# 1_54in.net
KiCad netlist of a schematic drawn in EAGLE
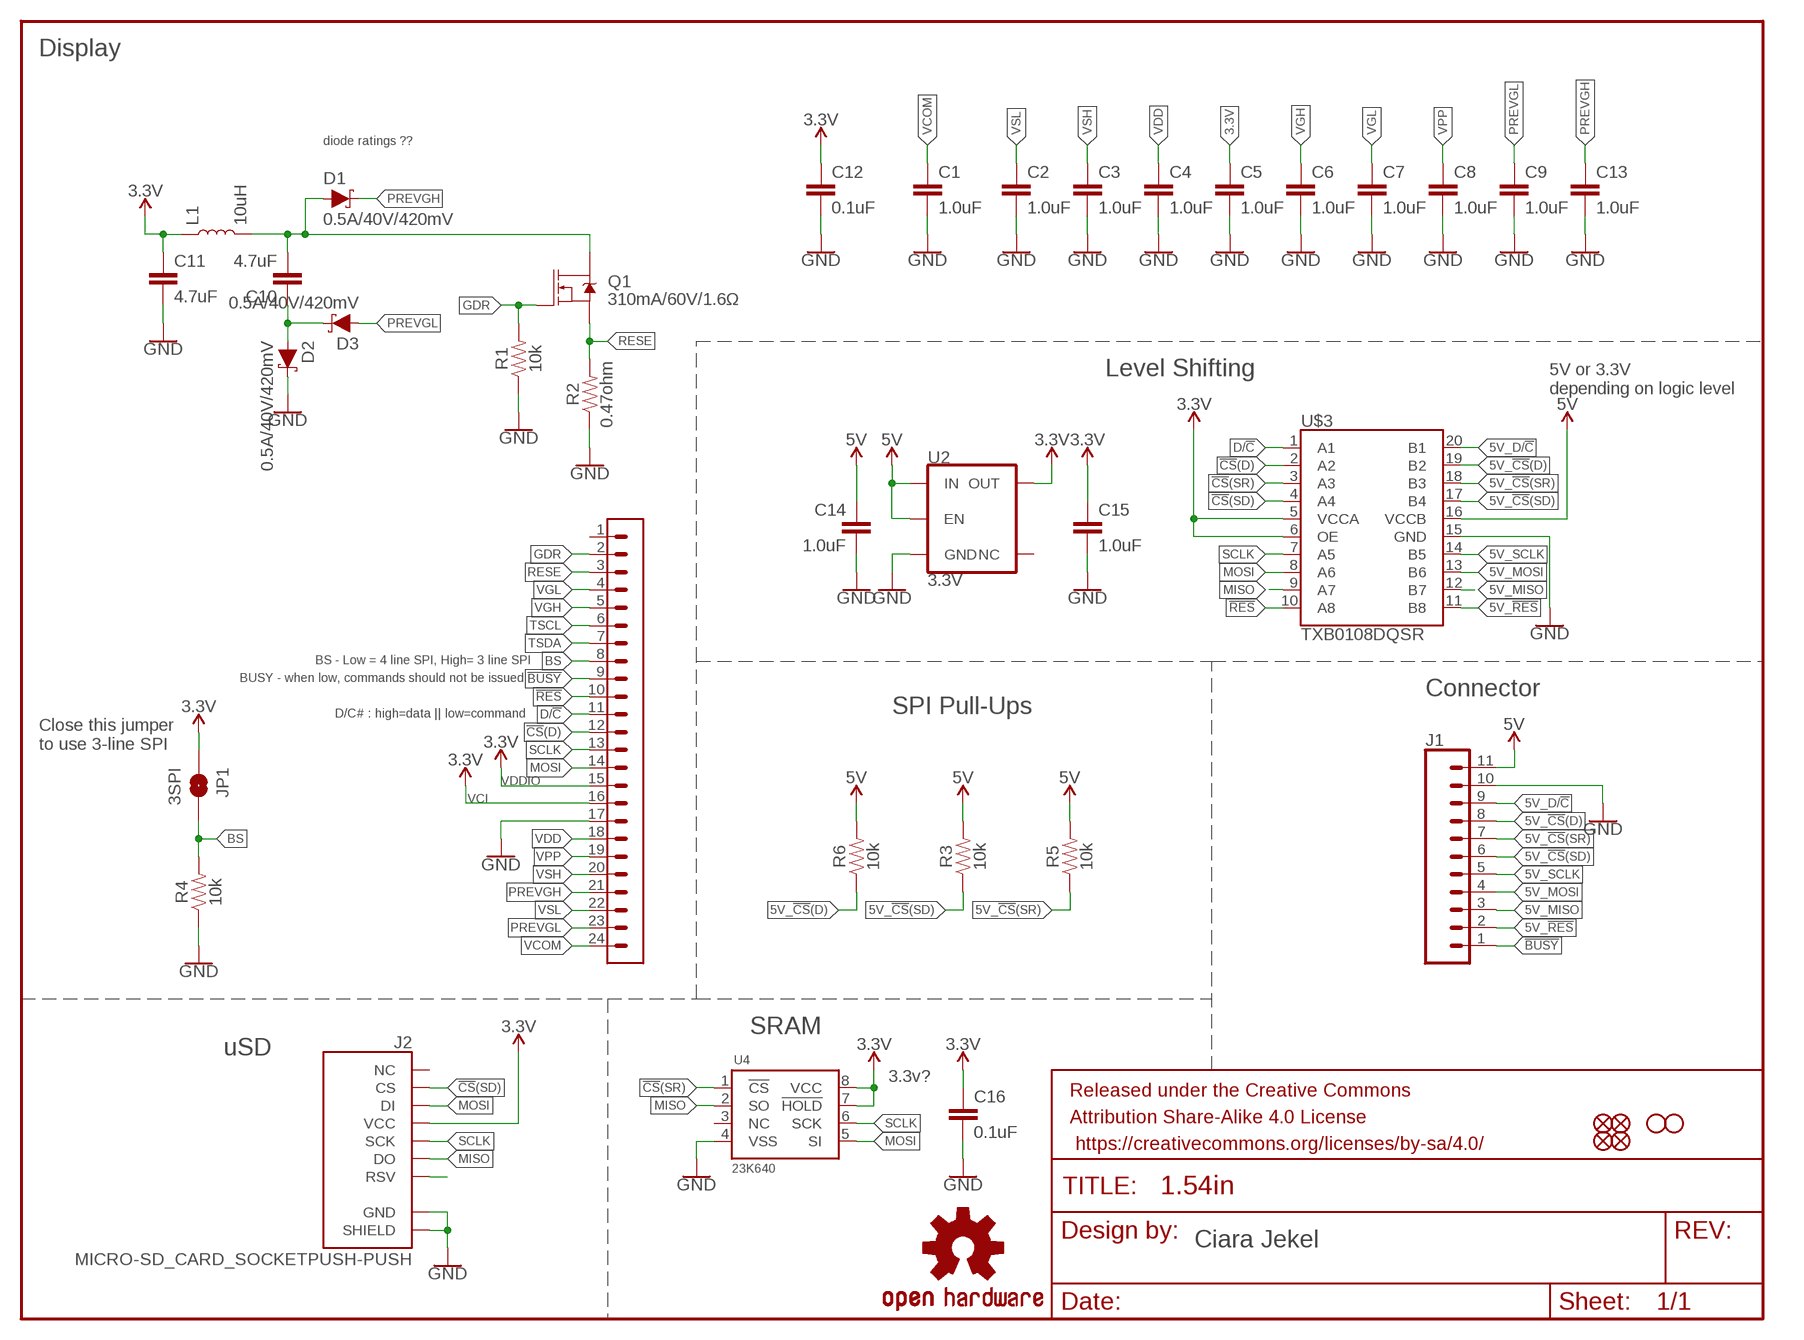
[diagram p0: schematic, sheet 1]

(export (version "E")
  (design (tool "Eeschema 10.0.6"))
  (components
    (comp (ref "C1")
      (value "1.0uF")
      (footprint "eagle-import:0603")
      (libsource (lib "eagle-import") (part "1.0UF-0603-16V-10%"))
    )
    (comp (ref "C2")
      (value "1.0uF")
      (footprint "eagle-import:0805")
      (libsource (lib "eagle-import") (part "1.0UF-0805-25V-10%"))
    )
    (comp (ref "C3")
      (value "1.0uF")
      (footprint "eagle-import:0805")
      (libsource (lib "eagle-import") (part "1.0UF-0805-25V-10%"))
    )
    (comp (ref "C4")
      (value "1.0uF")
      (footprint "eagle-import:0805")
      (libsource (lib "eagle-import") (part "1.0UF-0805-25V-10%"))
    )
    (comp (ref "C5")
      (value "1.0uF")
      (footprint "eagle-import:0805")
      (libsource (lib "eagle-import") (part "1.0UF-0805-25V-10%"))
    )
    (comp (ref "C6")
      (value "1.0uF")
      (footprint "eagle-import:0805")
      (libsource (lib "eagle-import") (part "1.0UF-0805-25V-10%"))
    )
    (comp (ref "C7")
      (value "1.0uF")
      (footprint "eagle-import:0805")
      (libsource (lib "eagle-import") (part "1.0UF-0805-25V-10%"))
    )
    (comp (ref "C8")
      (value "1.0uF")
      (footprint "eagle-import:0805")
      (libsource (lib "eagle-import") (part "1.0UF-0805-25V-10%"))
    )
    (comp (ref "C9")
      (value "1.0uF")
      (footprint "eagle-import:0805")
      (libsource (lib "eagle-import") (part "1.0UF-0805-25V-10%"))
    )
    (comp (ref "C10")
      (value "4.7uF")
      (footprint "eagle-import:0805")
      (libsource (lib "eagle-import") (part "22UF-0805-6.3V-20%"))
    )
    (comp (ref "C11")
      (value "4.7uF")
      (footprint "eagle-import:0805")
      (libsource (lib "eagle-import") (part "22UF-0805-6.3V-20%"))
    )
    (comp (ref "C12")
      (value "0.1uF")
      (footprint "eagle-import:0603")
      (libsource (lib "eagle-import") (part "0.1UF-0603-25V-(+80/-20%)"))
    )
    (comp (ref "C13")
      (value "1.0uF")
      (footprint "eagle-import:0805")
      (libsource (lib "eagle-import") (part "1.0UF-0805-25V-10%"))
    )
    (comp (ref "C14")
      (value "1.0uF")
      (footprint "eagle-import:0603")
      (libsource (lib "eagle-import") (part "1.0UF-0603-16V-10%"))
    )
    (comp (ref "C15")
      (value "1.0uF")
      (footprint "eagle-import:0603")
      (libsource (lib "eagle-import") (part "1.0UF-0603-16V-10%"))
    )
    (comp (ref "C16")
      (value "0.1uF")
      (footprint "eagle-import:0603")
      (libsource (lib "eagle-import") (part "0.1UF-0603-25V-(+80/-20%)"))
    )
    (comp (ref "D1")
      (value "0.5A/40V/420mV")
      (footprint "eagle-import:SOD-323")
      (libsource (lib "eagle-import") (part "DIODE-SCHOTTKY-PMEG4005EJ"))
    )
    (comp (ref "D2")
      (value "0.5A/40V/420mV")
      (footprint "eagle-import:SOD-323")
      (libsource (lib "eagle-import") (part "DIODE-SCHOTTKY-PMEG4005EJ"))
    )
    (comp (ref "D3")
      (value "0.5A/40V/420mV")
      (footprint "eagle-import:SOD-323")
      (libsource (lib "eagle-import") (part "DIODE-SCHOTTKY-PMEG4005EJ"))
    )
    (comp (ref "FD1")
      (value "FIDUCIALUFIDUCIAL")
      (footprint "eagle-import:FIDUCIAL-MICRO")
      (libsource (lib "eagle-import") (part "FIDUCIALUFIDUCIAL"))
    )
    (comp (ref "FD2")
      (value "FIDUCIALUFIDUCIAL")
      (footprint "eagle-import:FIDUCIAL-MICRO")
      (libsource (lib "eagle-import") (part "FIDUCIALUFIDUCIAL"))
    )
    (comp (ref "FD3")
      (value "FIDUCIALUFIDUCIAL")
      (footprint "eagle-import:FIDUCIAL-MICRO")
      (libsource (lib "eagle-import") (part "FIDUCIALUFIDUCIAL"))
    )
    (comp (ref "FD4")
      (value "FIDUCIALUFIDUCIAL")
      (footprint "eagle-import:FIDUCIAL-MICRO")
      (libsource (lib "eagle-import") (part "FIDUCIALUFIDUCIAL"))
    )
    (comp (ref "FRAME1")
      (value "FRAME-LETTER")
      (footprint "eagle-import:CREATIVE_COMMONS")
      (libsource (lib "eagle-import") (part "FRAME-LETTER"))
    )
    (comp (ref "H1")
      (value "STAND-OFF")
      (footprint "eagle-import:STAND-OFF")
      (libsource (lib "eagle-import") (part "STAND-OFF"))
    )
    (comp (ref "H2")
      (value "STAND-OFF")
      (footprint "eagle-import:STAND-OFF")
      (libsource (lib "eagle-import") (part "STAND-OFF"))
    )
    (comp (ref "J1")
      (value "CONN_111X11_NO_SILK")
      (footprint "eagle-import:1X11_NO_SILK")
      (libsource (lib "eagle-import") (part "CONN_111X11_NO_SILK"))
    )
    (comp (ref "J2")
      (value "MICRO-SD_CARD_SOCKETPUSH-PUSH")
      (footprint "eagle-import:MICRO-SD-SOCKET")
      (libsource (lib "eagle-import") (part "MICRO-SD_CARD_SOCKETPUSH-PUSH"))
    )
    (comp (ref "JP1")
      (value "3SPI")
      (footprint "eagle-import:SMT-JUMPER_2_NO_SILK")
      (libsource (lib "eagle-import") (part "JUMPER-SMT_2_NO_SILK"))
    )
    (comp (ref "L1")
      (value "10uH")
      (footprint "eagle-import:INDUCTOR_4.7UH")
      (libsource (lib "eagle-import") (part "INDUCTOR-CDRH-10UH"))
    )
    (comp (ref "LOGO1")
      (value "OSHW-LOGOS")
      (footprint "eagle-import:OSHW-LOGO-S")
      (libsource (lib "eagle-import") (part "OSHW-LOGOS"))
    )
    (comp (ref "Q1")
      (value "310mA/60V/1.6Ω")
      (footprint "eagle-import:SOT323")
      (libsource (lib "eagle-import") (part "MOSFET-NCH-2N7002PW"))
    )
    (comp (ref "R1")
      (value "10k")
      (footprint "eagle-import:0603")
      (libsource (lib "eagle-import") (part "10KOHM-0603-1/10W-1%"))
    )
    (comp (ref "R2")
      (value "0.47ohm")
      (footprint "eagle-import:0603")
      (libsource (lib "eagle-import") (part "RESISTOR0603"))
    )
    (comp (ref "R3")
      (value "10k")
      (footprint "eagle-import:0603")
      (libsource (lib "eagle-import") (part "10KOHM-0603-1/10W-1%"))
    )
    (comp (ref "R4")
      (value "10k")
      (footprint "eagle-import:0603")
      (libsource (lib "eagle-import") (part "10KOHM-0603-1/10W-1%"))
    )
    (comp (ref "R5")
      (value "10k")
      (footprint "eagle-import:0603")
      (libsource (lib "eagle-import") (part "10KOHM-0603-1/10W-1%"))
    )
    (comp (ref "R6")
      (value "10k")
      (footprint "eagle-import:0603")
      (libsource (lib "eagle-import") (part "10KOHM-0603-1/10W-1%"))
    )
    (comp (ref "U$1")
      (value "24_PIN_FPC_0.5MM")
      (footprint "eagle-import:24_PIN_FPC_0.5MM")
      (libsource (lib "eagle-import") (part "24_PIN_FPC_0.5MM"))
    )
    (comp (ref "U$3")
      (value "TXB0108DQSR")
      (footprint "eagle-import:UFDFN-20")
      (libsource (lib "eagle-import") (part "TXB0108"))
    )
    (comp (ref "U2")
      (value "3.3V")
      (footprint "eagle-import:SOT23-5")
      (libsource (lib "eagle-import") (part "V_REG_AP2112K-3.3V"))
    )
    (comp (ref "U4")
      (value "23K640")
      (footprint "eagle-import:SO08")
      (libsource (lib "eagle-import") (part "23K640"))
    )
  )
  (nets
    (net (code "1") (name "/5V_D{slash}~{C}") (class "Default")
      (node (ref "J1") (pin "9") (pinfunction "9_9") (pintype "passive"))
      (node (ref "U$3") (pin "20") (pinfunction "B1_20") (pintype "bidirectional"))
    )
    (net (code "2") (name "/5V_~{CS}(D)") (class "Default")
      (node (ref "J1") (pin "8") (pinfunction "8_8") (pintype "passive"))
      (node (ref "R6") (pin "1") (pinfunction "1_1") (pintype "passive"))
      (node (ref "U$3") (pin "19") (pinfunction "B2_19") (pintype "bidirectional"))
    )
    (net (code "3") (name "/5V_~{CS}(SD)") (class "Default")
      (node (ref "J1") (pin "6") (pinfunction "6_6") (pintype "passive"))
      (node (ref "R3") (pin "1") (pinfunction "1_1") (pintype "passive"))
      (node (ref "U$3") (pin "17") (pinfunction "B4_17") (pintype "bidirectional"))
    )
    (net (code "4") (name "/5V_~{CS}(SR)") (class "Default")
      (node (ref "J1") (pin "7") (pinfunction "7_7") (pintype "passive"))
      (node (ref "R5") (pin "1") (pinfunction "1_1") (pintype "passive"))
      (node (ref "U$3") (pin "18") (pinfunction "B3_18") (pintype "bidirectional"))
    )
    (net (code "5") (name "/5V_~{RES}") (class "Default")
      (node (ref "J1") (pin "2") (pinfunction "2_2") (pintype "passive"))
      (node (ref "U$3") (pin "11") (pinfunction "B8_11") (pintype "bidirectional"))
    )
    (net (code "6") (name "/D{slash}~{C}") (class "Default")
      (node (ref "U$1") (pin "11") (pinfunction "11_11") (pintype "bidirectional"))
      (node (ref "U$3") (pin "1") (pinfunction "A1_1") (pintype "bidirectional"))
    )
    (net (code "7") (name "/~{BUSY}") (class "Default")
      (node (ref "J1") (pin "1") (pinfunction "1_1") (pintype "passive"))
      (node (ref "U$1") (pin "9") (pinfunction "9_9") (pintype "bidirectional"))
    )
    (net (code "8") (name "/~{CS}(D)") (class "Default")
      (node (ref "U$1") (pin "12") (pinfunction "12_12") (pintype "bidirectional"))
      (node (ref "U$3") (pin "2") (pinfunction "A2_2") (pintype "bidirectional"))
    )
    (net (code "9") (name "/~{CS}(SD)") (class "Default")
      (node (ref "J2") (pin "CS") (pinfunction "CS_CS") (pintype "bidirectional"))
      (node (ref "U$3") (pin "4") (pinfunction "A4_4") (pintype "bidirectional"))
    )
    (net (code "10") (name "/~{CS}(SR)") (class "Default")
      (node (ref "U$3") (pin "3") (pinfunction "A3_3") (pintype "bidirectional"))
      (node (ref "U4") (pin "1") (pinfunction "~{CS}_1") (pintype "bidirectional"))
    )
    (net (code "11") (name "/~{RES}") (class "Default")
      (node (ref "U$1") (pin "10") (pinfunction "10_10") (pintype "bidirectional"))
      (node (ref "U$3") (pin "10") (pinfunction "A8_10") (pintype "bidirectional"))
    )
    (net (code "12") (name "3.3V") (class "Default")
      (node (ref "C11") (pin "1") (pinfunction "1_1") (pintype "passive"))
      (node (ref "C12") (pin "1") (pinfunction "1_1") (pintype "passive"))
      (node (ref "C15") (pin "1") (pinfunction "1_1") (pintype "passive"))
      (node (ref "C16") (pin "1") (pinfunction "1_1") (pintype "passive"))
      (node (ref "C5") (pin "1") (pinfunction "1_1") (pintype "passive"))
      (node (ref "J2") (pin "VCC") (pinfunction "VCC_VCC") (pintype "bidirectional"))
      (node (ref "JP1") (pin "1") (pinfunction "1_1") (pintype "passive"))
      (node (ref "L1") (pin "P$1") (pinfunction "1_P$1") (pintype "passive"))
      (node (ref "U$1") (pin "15") (pinfunction "15_15") (pintype "bidirectional"))
      (node (ref "U$1") (pin "16") (pinfunction "16_16") (pintype "bidirectional"))
      (node (ref "U$3") (pin "5") (pinfunction "VCCA_5") (pintype "bidirectional"))
      (node (ref "U$3") (pin "6") (pinfunction "OE_6") (pintype "bidirectional"))
      (node (ref "U2") (pin "5") (pinfunction "OUT_5") (pintype "passive"))
      (node (ref "U4") (pin "7") (pinfunction "~{HOLD}_7") (pintype "bidirectional"))
      (node (ref "U4") (pin "8") (pinfunction "VCC_8") (pintype "bidirectional"))
    )
    (net (code "13") (name "5V") (class "Default")
      (node (ref "C14") (pin "1") (pinfunction "1_1") (pintype "passive"))
      (node (ref "J1") (pin "11") (pinfunction "11_11") (pintype "passive"))
      (node (ref "R3") (pin "2") (pinfunction "2_2") (pintype "passive"))
      (node (ref "R5") (pin "2") (pinfunction "2_2") (pintype "passive"))
      (node (ref "R6") (pin "2") (pinfunction "2_2") (pintype "passive"))
      (node (ref "U$3") (pin "16") (pinfunction "VCCB_16") (pintype "bidirectional"))
      (node (ref "U2") (pin "1") (pinfunction "IN_1") (pintype "input"))
      (node (ref "U2") (pin "3") (pinfunction "EN_3") (pintype "input"))
    )
    (net (code "14") (name "5V_MISO") (class "Default")
      (node (ref "J1") (pin "3") (pinfunction "3_3") (pintype "passive"))
      (node (ref "U$3") (pin "12") (pinfunction "B7_12") (pintype "bidirectional"))
    )
    (net (code "15") (name "5V_MOSI") (class "Default")
      (node (ref "J1") (pin "4") (pinfunction "4_4") (pintype "passive"))
      (node (ref "U$3") (pin "13") (pinfunction "B6_13") (pintype "bidirectional"))
    )
    (net (code "16") (name "5V_SCLK") (class "Default")
      (node (ref "J1") (pin "5") (pinfunction "5_5") (pintype "passive"))
      (node (ref "U$3") (pin "14") (pinfunction "B5_14") (pintype "bidirectional"))
    )
    (net (code "17") (name "BS") (class "Default")
      (node (ref "JP1") (pin "2") (pinfunction "2_2") (pintype "passive"))
      (node (ref "R4") (pin "2") (pinfunction "2_2") (pintype "passive"))
      (node (ref "U$1") (pin "8") (pinfunction "8_8") (pintype "bidirectional"))
    )
    (net (code "18") (name "GDR") (class "Default")
      (node (ref "Q1") (pin "1") (pinfunction "G_1") (pintype "bidirectional"))
      (node (ref "R1") (pin "2") (pinfunction "2_2") (pintype "passive"))
      (node (ref "U$1") (pin "2") (pinfunction "2_2") (pintype "bidirectional"))
    )
    (net (code "19") (name "GND") (class "Default")
      (node (ref "C1") (pin "2") (pinfunction "2_2") (pintype "passive"))
      (node (ref "C11") (pin "2") (pinfunction "2_2") (pintype "passive"))
      (node (ref "C12") (pin "2") (pinfunction "2_2") (pintype "passive"))
      (node (ref "C13") (pin "2") (pinfunction "2_2") (pintype "passive"))
      (node (ref "C14") (pin "2") (pinfunction "2_2") (pintype "passive"))
      (node (ref "C15") (pin "2") (pinfunction "2_2") (pintype "passive"))
      (node (ref "C16") (pin "2") (pinfunction "2_2") (pintype "passive"))
      (node (ref "C2") (pin "2") (pinfunction "2_2") (pintype "passive"))
      (node (ref "C3") (pin "2") (pinfunction "2_2") (pintype "passive"))
      (node (ref "C4") (pin "2") (pinfunction "2_2") (pintype "passive"))
      (node (ref "C5") (pin "2") (pinfunction "2_2") (pintype "passive"))
      (node (ref "C6") (pin "2") (pinfunction "2_2") (pintype "passive"))
      (node (ref "C7") (pin "2") (pinfunction "2_2") (pintype "passive"))
      (node (ref "C8") (pin "2") (pinfunction "2_2") (pintype "passive"))
      (node (ref "C9") (pin "2") (pinfunction "2_2") (pintype "passive"))
      (node (ref "D2") (pin "C") (pinfunction "C_C") (pintype "passive"))
      (node (ref "J1") (pin "10") (pinfunction "10_10") (pintype "passive"))
      (node (ref "J2") (pin "CD1") (pinfunction "SHIELD_CD1") (pintype "bidirectional"))
      (node (ref "J2") (pin "GND") (pinfunction "GND_GND") (pintype "bidirectional"))
      (node (ref "R1") (pin "1") (pinfunction "1_1") (pintype "passive"))
      (node (ref "R2") (pin "1") (pinfunction "1_1") (pintype "passive"))
      (node (ref "R4") (pin "1") (pinfunction "1_1") (pintype "passive"))
      (node (ref "U$1") (pin "17") (pinfunction "17_17") (pintype "bidirectional"))
      (node (ref "U$3") (pin "15") (pinfunction "GND_15") (pintype "bidirectional"))
      (node (ref "U2") (pin "2") (pinfunction "GND_2") (pintype "input"))
      (node (ref "U4") (pin "4") (pinfunction "VSS_4") (pintype "bidirectional"))
    )
    (net (code "20") (name "MISO") (class "Default")
      (node (ref "J2") (pin "DO") (pinfunction "DO_DO") (pintype "bidirectional"))
      (node (ref "U$3") (pin "9") (pinfunction "A7_9") (pintype "bidirectional"))
      (node (ref "U4") (pin "2") (pinfunction "SO_2") (pintype "bidirectional"))
    )
    (net (code "21") (name "MOSI") (class "Default")
      (node (ref "J2") (pin "DI") (pinfunction "DI_DI") (pintype "bidirectional"))
      (node (ref "U$1") (pin "14") (pinfunction "14_14") (pintype "bidirectional"))
      (node (ref "U$3") (pin "8") (pinfunction "A6_8") (pintype "bidirectional"))
      (node (ref "U4") (pin "5") (pinfunction "SI_5") (pintype "bidirectional"))
    )
    (net (code "22") (name "Net-(C10-Pad1)") (class "Default")
      (node (ref "C10") (pin "1") (pinfunction "1_1") (pintype "passive"))
      (node (ref "D2") (pin "A") (pinfunction "A_A") (pintype "passive"))
      (node (ref "D3") (pin "C") (pinfunction "C_C") (pintype "passive"))
    )
    (net (code "23") (name "Net-(L1-2)") (class "Default")
      (node (ref "C10") (pin "2") (pinfunction "2_2") (pintype "passive"))
      (node (ref "D1") (pin "A") (pinfunction "A_A") (pintype "passive"))
      (node (ref "L1") (pin "P$2") (pinfunction "2_P$2") (pintype "passive"))
      (node (ref "Q1") (pin "3") (pinfunction "D_3") (pintype "bidirectional"))
    )
    (net (code "24") (name "PREVGH") (class "Default")
      (node (ref "C13") (pin "1") (pinfunction "1_1") (pintype "passive"))
      (node (ref "D1") (pin "C") (pinfunction "C_C") (pintype "passive"))
      (node (ref "U$1") (pin "21") (pinfunction "21_21") (pintype "bidirectional"))
    )
    (net (code "25") (name "PREVGL") (class "Default")
      (node (ref "C9") (pin "1") (pinfunction "1_1") (pintype "passive"))
      (node (ref "D3") (pin "A") (pinfunction "A_A") (pintype "passive"))
      (node (ref "U$1") (pin "23") (pinfunction "23_23") (pintype "bidirectional"))
    )
    (net (code "26") (name "RESE") (class "Default")
      (node (ref "Q1") (pin "2") (pinfunction "S_2") (pintype "bidirectional"))
      (node (ref "R2") (pin "2") (pinfunction "2_2") (pintype "passive"))
      (node (ref "U$1") (pin "3") (pinfunction "3_3") (pintype "bidirectional"))
    )
    (net (code "27") (name "SCLK") (class "Default")
      (node (ref "J2") (pin "SCLK") (pinfunction "SCK_SCLK") (pintype "bidirectional"))
      (node (ref "U$1") (pin "13") (pinfunction "13_13") (pintype "bidirectional"))
      (node (ref "U$3") (pin "7") (pinfunction "A5_7") (pintype "bidirectional"))
      (node (ref "U4") (pin "6") (pinfunction "SCK_6") (pintype "bidirectional"))
    )
    (net (code "28") (name "TSCL") (class "Default")
      (node (ref "U$1") (pin "6") (pinfunction "6_6") (pintype "bidirectional"))
    )
    (net (code "29") (name "TSDA") (class "Default")
      (node (ref "U$1") (pin "7") (pinfunction "7_7") (pintype "bidirectional"))
    )
    (net (code "30") (name "VCOM") (class "Default")
      (node (ref "C1") (pin "1") (pinfunction "1_1") (pintype "passive"))
      (node (ref "U$1") (pin "24") (pinfunction "24_24") (pintype "bidirectional"))
    )
    (net (code "31") (name "VDD") (class "Default")
      (node (ref "C4") (pin "1") (pinfunction "1_1") (pintype "passive"))
      (node (ref "U$1") (pin "18") (pinfunction "18_18") (pintype "bidirectional"))
    )
    (net (code "32") (name "VGH") (class "Default")
      (node (ref "C6") (pin "1") (pinfunction "1_1") (pintype "passive"))
      (node (ref "U$1") (pin "5") (pinfunction "5_5") (pintype "bidirectional"))
    )
    (net (code "33") (name "VGL") (class "Default")
      (node (ref "C7") (pin "1") (pinfunction "1_1") (pintype "passive"))
      (node (ref "U$1") (pin "4") (pinfunction "4_4") (pintype "bidirectional"))
    )
    (net (code "34") (name "VPP") (class "Default")
      (node (ref "C8") (pin "1") (pinfunction "1_1") (pintype "passive"))
      (node (ref "U$1") (pin "19") (pinfunction "19_19") (pintype "bidirectional"))
    )
    (net (code "35") (name "VSH") (class "Default")
      (node (ref "C3") (pin "1") (pinfunction "1_1") (pintype "passive"))
      (node (ref "U$1") (pin "20") (pinfunction "20_20") (pintype "bidirectional"))
    )
    (net (code "36") (name "VSL") (class "Default")
      (node (ref "C2") (pin "1") (pinfunction "1_1") (pintype "passive"))
      (node (ref "U$1") (pin "22") (pinfunction "22_22") (pintype "bidirectional"))
    )
    (net (code "37") (name "unconnected-(J2-NC-PadRSV2)") (class "Default")
      (node (ref "J2") (pin "RSV2") (pinfunction "NC_RSV2") (pintype "bidirectional"))
    )
    (net (code "38") (name "unconnected-(J2-RSV-PadRSV1)") (class "Default")
      (node (ref "J2") (pin "RSV1") (pinfunction "RSV_RSV1") (pintype "bidirectional"))
    )
    (net (code "39") (name "unconnected-(U$1-Pad1)") (class "Default")
      (node (ref "U$1") (pin "1") (pinfunction "1_1") (pintype "bidirectional"))
    )
    (net (code "40") (name "unconnected-(U2-NC-Pad4)") (class "Default")
      (node (ref "U2") (pin "4") (pinfunction "NC_4") (pintype "no_connect"))
    )
    (net (code "41") (name "unconnected-(U4-NC-Pad3)") (class "Default")
      (node (ref "U4") (pin "3") (pinfunction "NC_3") (pintype "bidirectional"))
    )
  )
)
